# WS2812b_capa.net
KiCad netlist of a schematic drawn in Altium Designer
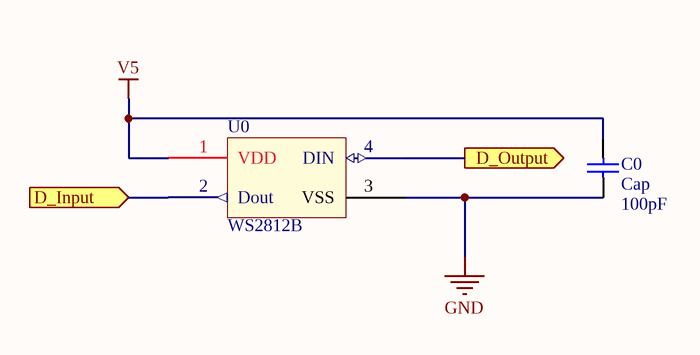
[diagram p0: WS2812b+capa.SchDoc]

(export (version "E")
  (design (tool "Eeschema 10.0.6"))
  (components
    (comp (ref "C0")
      (value "Cap")
      (footprint "RAD-0.3")
      (description "Capacitor")
      (fields (field (name "ALTIUM_VALUE") "100pF") (field (name "PUBLISHER") "Altium Limited"))
      (libsource (lib "Miscellaneous Devices") (part "Cap"))
    )
    (comp (ref "U0") (value "WS2812B") (footprint "WS2812b") (libsource (lib "Schlib1") (part "WS2812B")))
  )
  (nets
    (net (code "1") (name "/D_Input") (class "Default")
      (node (ref "U0") (pin "2") (pinfunction "Dout_2") (pintype "output"))
    )
    (net (code "2") (name "/D_Output") (class "Default")
      (node (ref "U0") (pin "4") (pinfunction "DIN_4") (pintype "bidirectional"))
    )
    (net (code "3") (name "GND") (class "Default")
      (node (ref "C0") (pin "1") (pinfunction "1_1") (pintype "passive"))
      (node (ref "U0") (pin "3") (pinfunction "VSS_3") (pintype "power_in"))
    )
    (net (code "4") (name "V5") (class "Default")
      (node (ref "C0") (pin "2") (pinfunction "2_2") (pintype "passive"))
      (node (ref "U0") (pin "1") (pinfunction "VDD_1") (pintype "power_in"))
    )
  )
)
